# ft245.net
KiCad netlist of a schematic drawn in Altium Designer
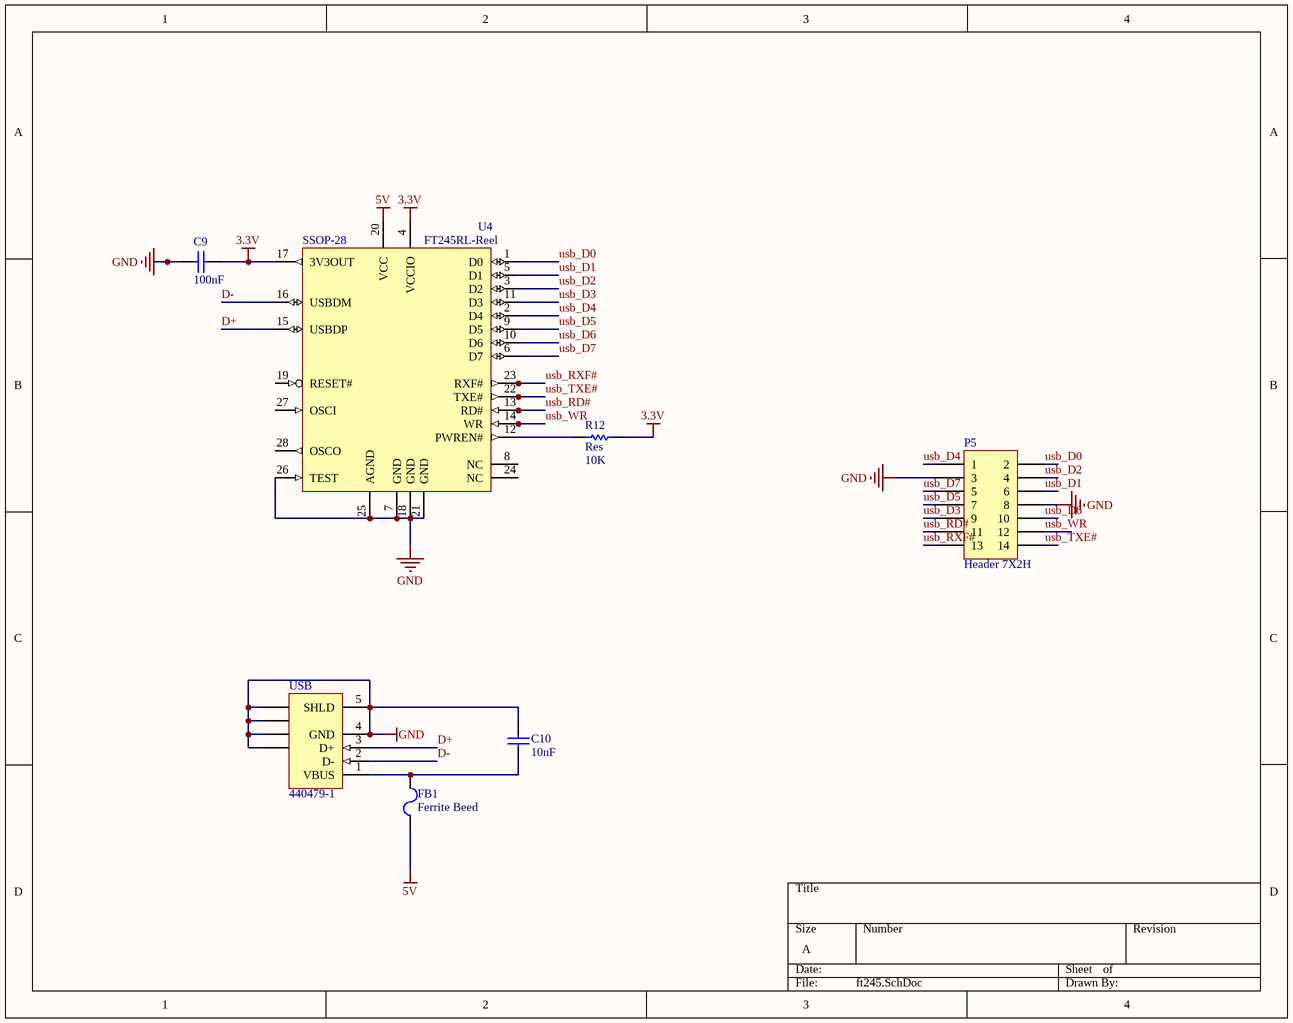
[diagram p0: ft245.SchDoc]

(export (version "E")
  (design (tool "Eeschema 10.0.6"))
  (components
    (comp (ref "C9")
      (value "100nF")
      (footprint "2012[0805]")
      (description "Capacitor")
      (fields (field (name "Comment") "Cap_UP") (field (name "PUBLISHER") "Altium Limited"))
      (libsource (lib "KN2CLib") (part "Cap_UP"))
    )
    (comp (ref "C10")
      (value "10nF")
      (footprint "2012[0805]")
      (description "Capacitor")
      (fields (field (name "Comment") "Cap_UP") (field (name "PUBLISHER") "Altium Limited"))
      (libsource (lib "KN2CLib") (part "Cap_UP"))
    )
    (comp (ref "FB1")
      (value "Ferrite Beed")
      (footprint "2012[0805]")
      (fields (field (name "PUBLISHER") "Altium Limited"))
      (libsource (lib "KN2CLib") (part "Ferrite Beed"))
    )
    (comp (ref "P5")
      (value "Header 7X2H")
      (footprint "HDR2X7H")
      (description "Header, 7-Pin, Dual row, Right Angle")
      (fields (field (name "PUBLISHER") "Altium Limited"))
      (libsource (lib "Miscellaneous Connectors") (part "Header 7X2H"))
    )
    (comp (ref "R12")
      (value "Res")
      (footprint "2012[0805]")
      (description "Semiconductor Resistor")
      (fields (field (name "ALTIUM_VALUE") "10K") (field (name "PUBLISHER") "Altium Limited"))
      (libsource (lib "KN2CLib") (part "Res"))
    )
    (comp (ref "U4")
      (value "FT245RL-Reel")
      (footprint "SSOP-28_N")
      (description "USB/Parallel FIFO Bi-Directional Data Transfer Chip, SSOP-28, Tape and Reel")
      (fields (field (name "PACKAGEREFERENCE") "SSOP-28") (field (name "PUBLISHER") "Altium Limited"))
      (libsource (lib "FTDI Communication FIFO") (part "FT245RL-Reel"))
    )
    (comp (ref "USB")
      (value "440479-1")
      (footprint "USB_Mini")
      (description "USB 2.0, Right Angle, SMT, AB Type, Receptacle, 5 Position, Black")
      (fields (field (name "PUBLISHER") "Altium Limited"))
      (libsource (lib "AMP Serial Bus USB") (part "440479-1"))
    )
  )
  (nets
    (net (code "1") (name "/D+") (class "Default")
      (node (ref "U4") (pin "15") (pinfunction "USBDP_15") (pintype "bidirectional"))
      (node (ref "USB") (pin "3") (pinfunction "D+_3") (pintype "input"))
    )
    (net (code "2") (name "/D-") (class "Default")
      (node (ref "U4") (pin "16") (pinfunction "USBDM_16") (pintype "bidirectional"))
      (node (ref "USB") (pin "2") (pinfunction "D-_2") (pintype "input"))
    )
    (net (code "3") (name "/usb_D0") (class "Default")
      (node (ref "P5") (pin "2") (pinfunction "2_2") (pintype "passive"))
      (node (ref "U4") (pin "1") (pinfunction "D0_1") (pintype "bidirectional"))
    )
    (net (code "4") (name "/usb_D1") (class "Default")
      (node (ref "P5") (pin "6") (pinfunction "6_6") (pintype "passive"))
      (node (ref "U4") (pin "5") (pinfunction "D1_5") (pintype "bidirectional"))
    )
    (net (code "5") (name "/usb_D2") (class "Default")
      (node (ref "P5") (pin "4") (pinfunction "4_4") (pintype "passive"))
      (node (ref "U4") (pin "3") (pinfunction "D2_3") (pintype "bidirectional"))
    )
    (net (code "6") (name "/usb_D3") (class "Default")
      (node (ref "P5") (pin "9") (pinfunction "9_9") (pintype "passive"))
      (node (ref "U4") (pin "11") (pinfunction "D3_11") (pintype "bidirectional"))
    )
    (net (code "7") (name "/usb_D4") (class "Default")
      (node (ref "P5") (pin "1") (pinfunction "1_1") (pintype "passive"))
      (node (ref "U4") (pin "2") (pinfunction "D4_2") (pintype "bidirectional"))
    )
    (net (code "8") (name "/usb_D5") (class "Default")
      (node (ref "P5") (pin "7") (pinfunction "7_7") (pintype "passive"))
      (node (ref "U4") (pin "9") (pinfunction "D5_9") (pintype "bidirectional"))
    )
    (net (code "9") (name "/usb_D6") (class "Default")
      (node (ref "P5") (pin "10") (pinfunction "10_10") (pintype "passive"))
      (node (ref "U4") (pin "10") (pinfunction "D6_10") (pintype "bidirectional"))
    )
    (net (code "10") (name "/usb_D7") (class "Default")
      (node (ref "P5") (pin "5") (pinfunction "5_5") (pintype "passive"))
      (node (ref "U4") (pin "6") (pinfunction "D7_6") (pintype "bidirectional"))
    )
    (net (code "11") (name "/usb_RD#") (class "Default")
      (node (ref "P5") (pin "11") (pinfunction "11_11") (pintype "passive"))
      (node (ref "U4") (pin "13") (pinfunction "RD#_13") (pintype "input"))
    )
    (net (code "12") (name "/usb_RXF#") (class "Default")
      (node (ref "P5") (pin "13") (pinfunction "13_13") (pintype "passive"))
      (node (ref "U4") (pin "23") (pinfunction "RXF#_23") (pintype "output"))
    )
    (net (code "13") (name "/usb_TXE#") (class "Default")
      (node (ref "P5") (pin "14") (pinfunction "14_14") (pintype "passive"))
      (node (ref "U4") (pin "22") (pinfunction "TXE#_22") (pintype "output"))
    )
    (net (code "14") (name "/usb_WR") (class "Default")
      (node (ref "P5") (pin "12") (pinfunction "12_12") (pintype "passive"))
      (node (ref "U4") (pin "14") (pinfunction "WR_14") (pintype "input"))
    )
    (net (code "15") (name "3.3V") (class "Default")
      (node (ref "C9") (pin "2") (pinfunction "2_2") (pintype "passive"))
      (node (ref "R12") (pin "2") (pinfunction "2_2") (pintype "passive"))
      (node (ref "U4") (pin "17") (pinfunction "3V3OUT_17") (pintype "output"))
      (node (ref "U4") (pin "4") (pinfunction "VCCIO_4") (pintype "power_in"))
    )
    (net (code "16") (name "5V") (class "Default")
      (node (ref "FB1") (pin "2") (pinfunction "2_2") (pintype "passive"))
      (node (ref "U4") (pin "20") (pinfunction "VCC_20") (pintype "power_in"))
    )
    (net (code "17") (name "GND") (class "Default")
      (node (ref "C10") (pin "2") (pinfunction "2_2") (pintype "passive"))
      (node (ref "C9") (pin "1") (pinfunction "1_1") (pintype "passive"))
      (node (ref "P5") (pin "3") (pinfunction "3_3") (pintype "passive"))
      (node (ref "P5") (pin "8") (pinfunction "8_8") (pintype "passive"))
      (node (ref "U4") (pin "18") (pinfunction "GND_18") (pintype "power_in"))
      (node (ref "U4") (pin "21") (pinfunction "GND_21") (pintype "power_in"))
      (node (ref "U4") (pin "25") (pinfunction "AGND_25") (pintype "power_in"))
      (node (ref "U4") (pin "26") (pinfunction "TEST_26") (pintype "input"))
      (node (ref "U4") (pin "7") (pinfunction "GND_7") (pintype "power_in"))
      (node (ref "USB") (pin "4") (pinfunction "GND_4") (pintype "power_in"))
      (node (ref "USB") (pin "5") (pinfunction "SHLD_5") (pintype "passive"))
      (node (ref "USB") (pin "6") (pinfunction "SHLD_6") (pintype "passive"))
      (node (ref "USB") (pin "7") (pinfunction "SHLD_7") (pintype "passive"))
      (node (ref "USB") (pin "8") (pinfunction "SHLD_8") (pintype "passive"))
      (node (ref "USB") (pin "9") (pinfunction "SHLD_9") (pintype "passive"))
    )
    (net (code "18") (name "Net-(U4-PWREN#)") (class "Default")
      (node (ref "R12") (pin "1") (pinfunction "1_1") (pintype "passive"))
      (node (ref "U4") (pin "12") (pinfunction "PWREN#_12") (pintype "output"))
    )
    (net (code "19") (name "Net-(USB-VBUS)") (class "Default")
      (node (ref "C10") (pin "1") (pinfunction "1_1") (pintype "passive"))
      (node (ref "FB1") (pin "1") (pinfunction "1_1") (pintype "passive"))
      (node (ref "USB") (pin "1") (pinfunction "VBUS_1") (pintype "power_in"))
    )
    (net (code "20") (name "unconnected-(U4-NC-Pad8)") (class "Default")
      (node (ref "U4") (pin "8") (pinfunction "NC_8") (pintype "passive"))
    )
    (net (code "21") (name "unconnected-(U4-NC-Pad24)") (class "Default")
      (node (ref "U4") (pin "24") (pinfunction "NC_24") (pintype "passive"))
    )
    (net (code "22") (name "unconnected-(U4-OSCI-Pad27)") (class "Default")
      (node (ref "U4") (pin "27") (pinfunction "OSCI_27") (pintype "input"))
    )
    (net (code "23") (name "unconnected-(U4-OSCO-Pad28)") (class "Default")
      (node (ref "U4") (pin "28") (pinfunction "OSCO_28") (pintype "output"))
    )
    (net (code "24") (name "unconnected-(U4-RESET#-Pad19)") (class "Default")
      (node (ref "U4") (pin "19") (pinfunction "RESET#_19") (pintype "input"))
    )
  )
)
